# MaTouch_Devkit_Strip_Driver_V1_1.net
KiCad netlist of a schematic drawn in EAGLE
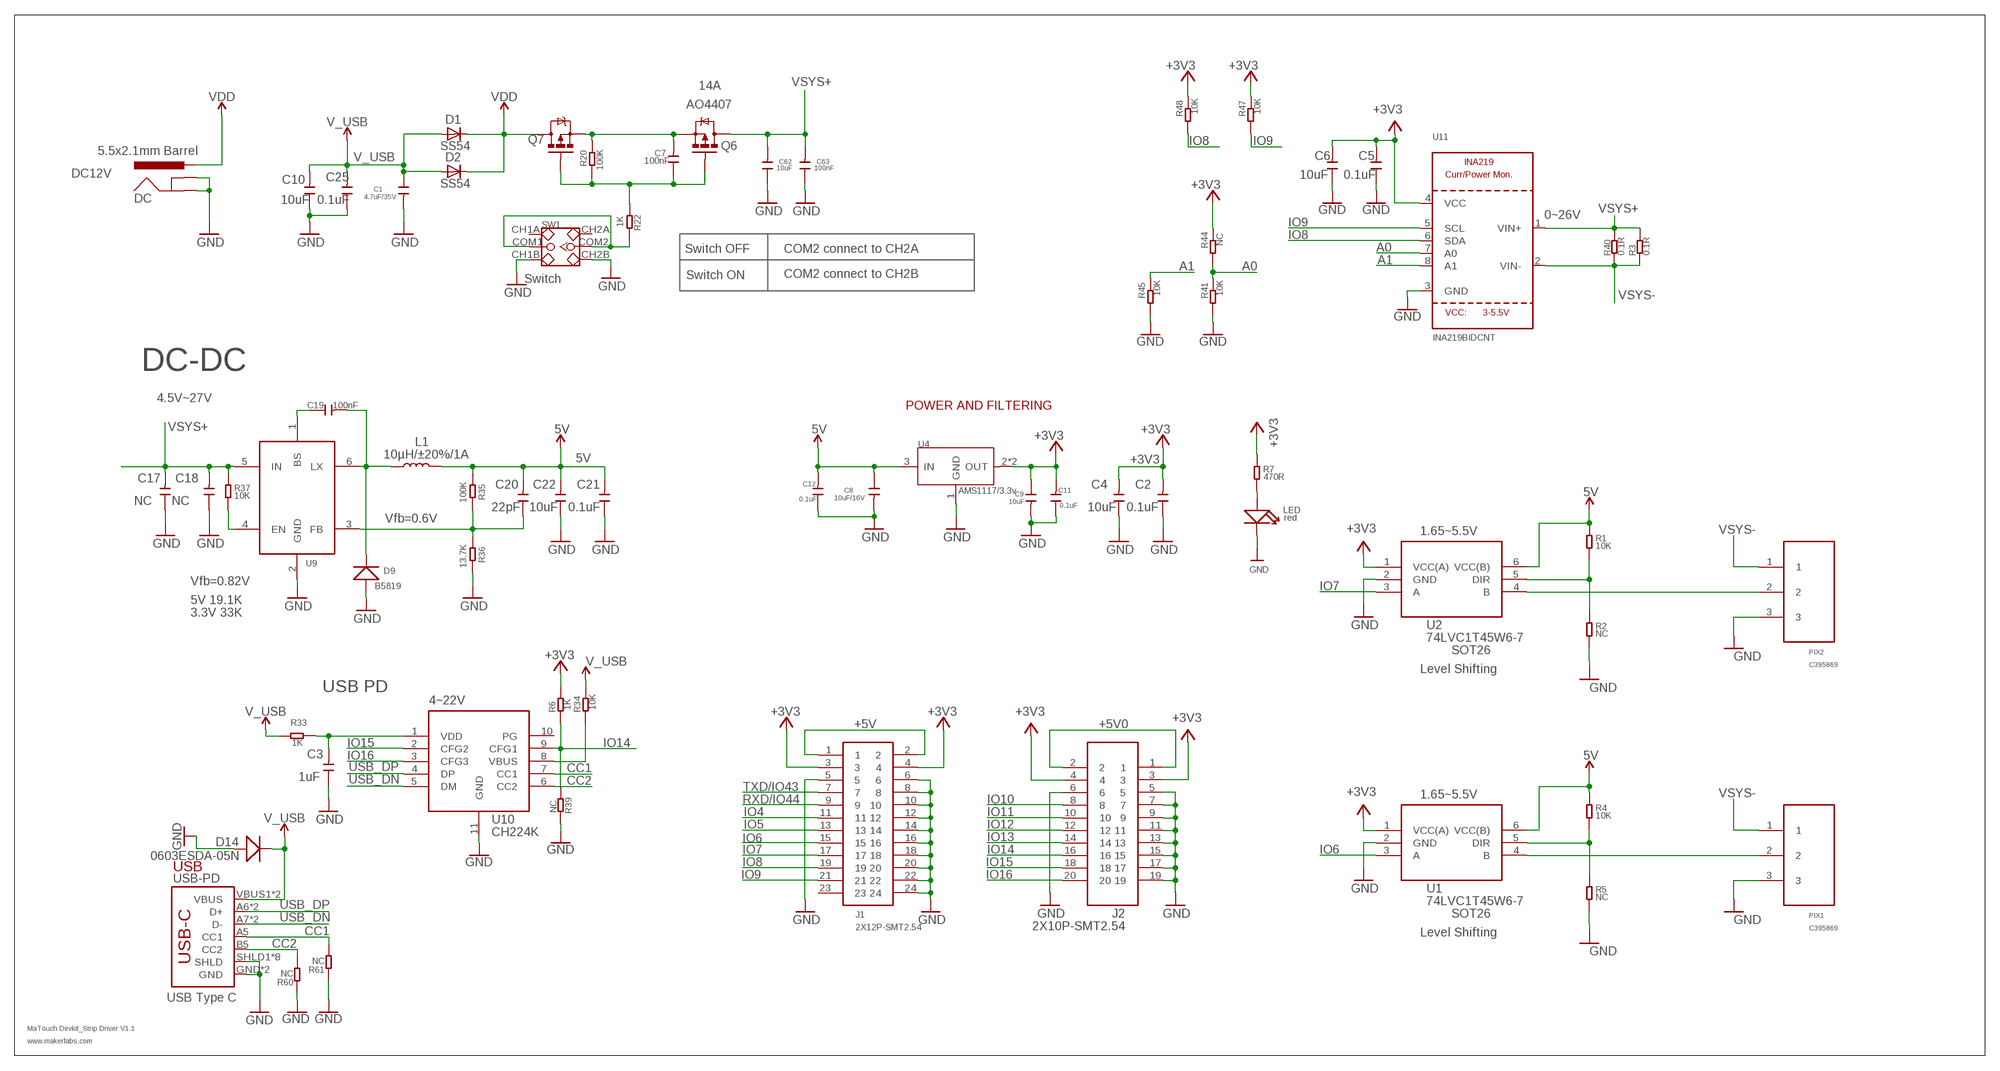
[diagram p0: schematic, sheet 1]

(export (version "E")
  (design (tool "Eeschema 10.0.6"))
  (components
    (comp (ref "C1")
      (value "4.7uF/35V")
      (footprint "eagle-import:0603")
      (libsource (lib "eagle-import") (part "C-0603"))
    )
    (comp (ref "C2")
      (value "0.1uF")
      (footprint "eagle-import:0603")
      (libsource (lib "eagle-import") (part "C-0603"))
    )
    (comp (ref "C3")
      (value "1uF")
      (footprint "eagle-import:0603")
      (libsource (lib "eagle-import") (part "C-0603"))
    )
    (comp (ref "C4")
      (value "10uF")
      (footprint "eagle-import:0603")
      (libsource (lib "eagle-import") (part "C-0603"))
    )
    (comp (ref "C5")
      (value "0.1uF")
      (footprint "eagle-import:0603")
      (libsource (lib "eagle-import") (part "C-0603"))
    )
    (comp (ref "C6")
      (value "10uF")
      (footprint "eagle-import:0603")
      (libsource (lib "eagle-import") (part "C-0603"))
    )
    (comp (ref "C7")
      (value "100nF")
      (footprint "eagle-import:0603")
      (libsource (lib "eagle-import") (part "C-0603"))
    )
    (comp (ref "C8")
      (value "10uF/16V")
      (footprint "eagle-import:0603")
      (libsource (lib "eagle-import") (part "C-0603"))
    )
    (comp (ref "C9")
      (value "10uF")
      (footprint "eagle-import:0603")
      (libsource (lib "eagle-import") (part "C-0603"))
    )
    (comp (ref "C10")
      (value "10uF")
      (footprint "eagle-import:0603")
      (libsource (lib "eagle-import") (part "C-0603"))
    )
    (comp (ref "C11")
      (value "0.1uF")
      (footprint "eagle-import:0603")
      (libsource (lib "eagle-import") (part "C-0603"))
    )
    (comp (ref "C12")
      (value "0.1uF")
      (footprint "eagle-import:0603")
      (libsource (lib "eagle-import") (part "C-0603"))
    )
    (comp (ref "C17")
      (value "NC")
      (footprint "eagle-import:0603")
      (libsource (lib "eagle-import") (part "C-0603"))
    )
    (comp (ref "C18")
      (value "NC")
      (footprint "eagle-import:0603")
      (libsource (lib "eagle-import") (part "C-0603"))
    )
    (comp (ref "C19")
      (value "100nF")
      (footprint "eagle-import:0603")
      (libsource (lib "eagle-import") (part "C-0603"))
    )
    (comp (ref "C20")
      (value "22pF")
      (footprint "eagle-import:0603")
      (libsource (lib "eagle-import") (part "C-0603"))
    )
    (comp (ref "C21")
      (value "0.1uF")
      (footprint "eagle-import:0603")
      (libsource (lib "eagle-import") (part "C-0603"))
    )
    (comp (ref "C22")
      (value "10uF")
      (footprint "eagle-import:0603")
      (libsource (lib "eagle-import") (part "C-0603"))
    )
    (comp (ref "C25")
      (value "0.1uF")
      (footprint "eagle-import:0603")
      (libsource (lib "eagle-import") (part "C-0603"))
    )
    (comp (ref "C62")
      (value "10uF")
      (footprint "eagle-import:0603")
      (libsource (lib "eagle-import") (part "C-0603"))
    )
    (comp (ref "C63")
      (value "100nF")
      (footprint "eagle-import:0603")
      (libsource (lib "eagle-import") (part "C-0603"))
    )
    (comp (ref "D1")
      (value "SS54")
      (footprint "eagle-import:DO-214AC")
      (libsource (lib "eagle-import") (part "DIODE-DO-214AC"))
    )
    (comp (ref "D2")
      (value "SS54")
      (footprint "eagle-import:DO-214AC")
      (libsource (lib "eagle-import") (part "DIODE-DO-214AC"))
    )
    (comp (ref "D9")
      (value "B5819")
      (footprint "eagle-import:SOD123")
      (libsource (lib "eagle-import") (part "D'1206'"))
    )
    (comp (ref "D14")
      (value "0603ESDA-05N")
      (footprint "eagle-import:DISCRETE_SOD523")
      (libsource (lib "eagle-import") (part "DISCRETE_D0603"))
    )
    (comp (ref "DC")
      (value "5.5x2.1mm Barrel")
      (footprint "eagle-import:POWER_JACK_SMD")
      (libsource (lib "eagle-import") (part "POWER_JACKSMD"))
    )
    (comp (ref "J1")
      (value "2X12P-SMT2.54")
      (footprint "eagle-import:2X12P-SMT2.54")
      (libsource (lib "eagle-import") (part "2X12P-SMT2.54"))
    )
    (comp (ref "J2")
      (value "2X10P-SMT2.54")
      (footprint "eagle-import:2X10P-SMT2.54")
      (libsource (lib "eagle-import") (part "2X10P-SMT2.54"))
    )
    (comp (ref "L1")
      (value "10µH/±20%/1A")
      (footprint "eagle-import:SRN6045")
      (libsource (lib "eagle-import") (part "INDUCTOR-SRN6045-33UH"))
    )
    (comp (ref "LED")
      (value "red")
      (footprint "eagle-import:DISCRETE_LED-0603")
      (libsource (lib "eagle-import") (part "DISCRETE_LED0603"))
    )
    (comp (ref "PIX1")
      (value "C395869")
      (footprint "eagle-import:PIN_3P")
      (libsource (lib "eagle-import") (part "C395869"))
    )
    (comp (ref "PIX2")
      (value "C395869")
      (footprint "eagle-import:PIN_3P")
      (libsource (lib "eagle-import") (part "C395869"))
    )
    (comp (ref "Q6")
      (value "MOSFET-PCHANNELFDS6675")
      (footprint "eagle-import:SO08")
      (libsource (lib "eagle-import") (part "MOSFET-PCHANNELFDS6675"))
    )
    (comp (ref "Q7")
      (value "MOSFET-PCHANNELFDS6675")
      (footprint "eagle-import:SO08")
      (libsource (lib "eagle-import") (part "MOSFET-PCHANNELFDS6675"))
    )
    (comp (ref "R1")
      (value "10K")
      (footprint "eagle-import:R0603")
      (libsource (lib "eagle-import") (part "R-0603"))
    )
    (comp (ref "R2")
      (value "NC")
      (footprint "eagle-import:R0603")
      (libsource (lib "eagle-import") (part "R-0603"))
    )
    (comp (ref "R3")
      (value "0.1R")
      (footprint "eagle-import:DISCRETE_R2512")
      (libsource (lib "eagle-import") (part "DISCRETE_R-2512"))
    )
    (comp (ref "R4")
      (value "10K")
      (footprint "eagle-import:R0603")
      (libsource (lib "eagle-import") (part "R-0603"))
    )
    (comp (ref "R5")
      (value "NC")
      (footprint "eagle-import:R0603")
      (libsource (lib "eagle-import") (part "R-0603"))
    )
    (comp (ref "R6")
      (value "1K")
      (footprint "eagle-import:R0603")
      (libsource (lib "eagle-import") (part "R-0603"))
    )
    (comp (ref "R7")
      (value "470R")
      (footprint "eagle-import:R0603")
      (libsource (lib "eagle-import") (part "R-0603"))
    )
    (comp (ref "R20")
      (value "100K")
      (footprint "eagle-import:R0603")
      (libsource (lib "eagle-import") (part "R-0603"))
    )
    (comp (ref "R22")
      (value "1K")
      (footprint "eagle-import:R0603")
      (libsource (lib "eagle-import") (part "R-0603"))
    )
    (comp (ref "R33")
      (value "1K")
      (footprint "eagle-import:R0603")
      (libsource (lib "eagle-import") (part "R-0603"))
    )
    (comp (ref "R34")
      (value "10K")
      (footprint "eagle-import:R0603")
      (libsource (lib "eagle-import") (part "R-0603"))
    )
    (comp (ref "R35")
      (value "100K")
      (footprint "eagle-import:R0603")
      (libsource (lib "eagle-import") (part "R-0603"))
    )
    (comp (ref "R36")
      (value "13.7K")
      (footprint "eagle-import:R0603")
      (libsource (lib "eagle-import") (part "R-0603"))
    )
    (comp (ref "R37")
      (value "10K")
      (footprint "eagle-import:R0603")
      (libsource (lib "eagle-import") (part "R-0603"))
    )
    (comp (ref "R39")
      (value "NC")
      (footprint "eagle-import:R0603")
      (libsource (lib "eagle-import") (part "R-0603"))
    )
    (comp (ref "R40")
      (value "0.1R")
      (footprint "eagle-import:DISCRETE_R2512")
      (libsource (lib "eagle-import") (part "DISCRETE_R-2512"))
    )
    (comp (ref "R41")
      (value "10K")
      (footprint "eagle-import:R0603")
      (libsource (lib "eagle-import") (part "R-0603"))
    )
    (comp (ref "R44")
      (value "NC")
      (footprint "eagle-import:R0603")
      (libsource (lib "eagle-import") (part "R-0603"))
    )
    (comp (ref "R45")
      (value "10K")
      (footprint "eagle-import:R0603")
      (libsource (lib "eagle-import") (part "R-0603"))
    )
    (comp (ref "R47")
      (value "10K")
      (footprint "eagle-import:R0603")
      (libsource (lib "eagle-import") (part "R-0603"))
    )
    (comp (ref "R48")
      (value "10K")
      (footprint "eagle-import:R0603")
      (libsource (lib "eagle-import") (part "R-0603"))
    )
    (comp (ref "R60")
      (value "NC")
      (footprint "eagle-import:DISCRETE_R0603")
      (libsource (lib "eagle-import") (part "DISCRETE_R-0603"))
    )
    (comp (ref "R61")
      (value "NC")
      (footprint "eagle-import:DISCRETE_R0603")
      (libsource (lib "eagle-import") (part "DISCRETE_R-0603"))
    )
    (comp (ref "SW1")
      (value "SWITCH-2CH-6P'90D'")
      (footprint "eagle-import:6P-2CH-2.54-9.0X3.6-90D")
      (libsource (lib "eagle-import") (part "SWITCH-2CH-6P'90D'"))
    )
    (comp (ref "U1")
      (value "74LVC1T45W6-7")
      (footprint "eagle-import:SOT-23-6")
      (libsource (lib "eagle-import") (part "74LVC1T45W6-7"))
    )
    (comp (ref "U2")
      (value "74LVC1T45W6-7")
      (footprint "eagle-import:SOT-23-6")
      (libsource (lib "eagle-import") (part "74LVC1T45W6-7"))
    )
    (comp (ref "U4")
      (value "AMS1117/3.3v")
      (footprint "eagle-import:SOT89")
      (libsource (lib "eagle-import") (part "LD1117'SOT89'"))
    )
    (comp (ref "U9")
      (value "SY8201ABC")
      (footprint "eagle-import:SOT-23-6")
      (libsource (lib "eagle-import") (part "SY8201ABC"))
    )
    (comp (ref "U10")
      (value "CH224K")
      (footprint "eagle-import:ESSOP-10-150MIL")
      (libsource (lib "eagle-import") (part "CH224K"))
    )
    (comp (ref "U11")
      (value "INA219BIDCNT")
      (footprint "eagle-import:SOT23-8")
      (libsource (lib "eagle-import") (part "INA219"))
    )
    (comp (ref "USB-PD")
      (value "USB_C5")
      (footprint "eagle-import:USB-C-16P-5")
      (libsource (lib "eagle-import") (part "USB_C5"))
    )
  )
  (nets
    (net (code "1") (name "+3V3") (class "Default")
      (node (ref "C11") (pin "2") (pinfunction "2_2") (pintype "passive"))
      (node (ref "C2") (pin "2") (pinfunction "2_2") (pintype "passive"))
      (node (ref "C4") (pin "2") (pinfunction "2_2") (pintype "passive"))
      (node (ref "C5") (pin "2") (pinfunction "2_2") (pintype "passive"))
      (node (ref "C6") (pin "2") (pinfunction "2_2") (pintype "passive"))
      (node (ref "C9") (pin "1") (pinfunction "1_1") (pintype "passive"))
      (node (ref "J1") (pin "3") (pinfunction "3_3") (pintype "bidirectional"))
      (node (ref "J1") (pin "4") (pinfunction "4_4") (pintype "bidirectional"))
      (node (ref "J2") (pin "3") (pinfunction "3_3") (pintype "bidirectional"))
      (node (ref "J2") (pin "4") (pinfunction "4_4") (pintype "bidirectional"))
      (node (ref "R44") (pin "2") (pinfunction "2_2") (pintype "passive"))
      (node (ref "R47") (pin "2") (pinfunction "2_2") (pintype "passive"))
      (node (ref "R48") (pin "2") (pinfunction "2_2") (pintype "passive"))
      (node (ref "R6") (pin "2") (pinfunction "2_2") (pintype "passive"))
      (node (ref "R7") (pin "1") (pinfunction "1_1") (pintype "passive"))
      (node (ref "U1") (pin "1") (pinfunction "VCC(A)_1") (pintype "bidirectional"))
      (node (ref "U11") (pin "4") (pinfunction "VCC_4") (pintype "power_in"))
      (node (ref "U2") (pin "1") (pinfunction "VCC(A)_1") (pintype "bidirectional"))
      (node (ref "U4") (pin "2") (pinfunction "OUT_2") (pintype "bidirectional"))
      (node (ref "U4") (pin "4") (pinfunction "OUT_4") (pintype "bidirectional"))
    )
    (net (code "2") (name "/+5V") (class "Default")
      (node (ref "J1") (pin "1") (pinfunction "1_1") (pintype "bidirectional"))
      (node (ref "J1") (pin "2") (pinfunction "2_2") (pintype "bidirectional"))
    )
    (net (code "3") (name "/+5V0") (class "Default")
      (node (ref "J2") (pin "1") (pinfunction "1_1") (pintype "bidirectional"))
      (node (ref "J2") (pin "2") (pinfunction "2_2") (pintype "bidirectional"))
    )
    (net (code "4") (name "/A0") (class "Default")
      (node (ref "R41") (pin "2") (pinfunction "2_2") (pintype "passive"))
      (node (ref "R44") (pin "1") (pinfunction "1_1") (pintype "passive"))
      (node (ref "U11") (pin "7") (pinfunction "A0_7") (pintype "bidirectional"))
    )
    (net (code "5") (name "/A1") (class "Default")
      (node (ref "R45") (pin "2") (pinfunction "2_2") (pintype "passive"))
      (node (ref "U11") (pin "8") (pinfunction "A1_8") (pintype "bidirectional"))
    )
    (net (code "6") (name "/CC1") (class "Default")
      (node (ref "R61") (pin "2") (pinfunction "2_2") (pintype "passive"))
      (node (ref "U10") (pin "7") (pinfunction "CC1_7") (pintype "bidirectional"))
      (node (ref "USB-PD") (pin "A5") (pinfunction "CC1_A5") (pintype "bidirectional"))
    )
    (net (code "7") (name "/CC2") (class "Default")
      (node (ref "R60") (pin "2") (pinfunction "2_2") (pintype "passive"))
      (node (ref "U10") (pin "6") (pinfunction "CC2_6") (pintype "bidirectional"))
      (node (ref "USB-PD") (pin "B5") (pinfunction "CC2_B5") (pintype "bidirectional"))
    )
    (net (code "8") (name "/IO4") (class "Default")
      (node (ref "J1") (pin "11") (pinfunction "11_11") (pintype "bidirectional"))
    )
    (net (code "9") (name "/IO5") (class "Default")
      (node (ref "J1") (pin "13") (pinfunction "13_13") (pintype "bidirectional"))
    )
    (net (code "10") (name "/IO6") (class "Default")
      (node (ref "J1") (pin "15") (pinfunction "15_15") (pintype "bidirectional"))
      (node (ref "U1") (pin "3") (pinfunction "A_3") (pintype "bidirectional"))
    )
    (net (code "11") (name "/IO7") (class "Default")
      (node (ref "J1") (pin "17") (pinfunction "17_17") (pintype "bidirectional"))
      (node (ref "U2") (pin "3") (pinfunction "A_3") (pintype "bidirectional"))
    )
    (net (code "12") (name "/IO8") (class "Default")
      (node (ref "J1") (pin "19") (pinfunction "19_19") (pintype "bidirectional"))
      (node (ref "R48") (pin "1") (pinfunction "1_1") (pintype "passive"))
      (node (ref "U11") (pin "6") (pinfunction "SDA_6") (pintype "bidirectional"))
    )
    (net (code "13") (name "/IO9") (class "Default")
      (node (ref "J1") (pin "21") (pinfunction "21_21") (pintype "bidirectional"))
      (node (ref "R47") (pin "1") (pinfunction "1_1") (pintype "passive"))
      (node (ref "U11") (pin "5") (pinfunction "SCL_5") (pintype "bidirectional"))
    )
    (net (code "14") (name "/IO10") (class "Default")
      (node (ref "J2") (pin "8") (pinfunction "8_8") (pintype "bidirectional"))
    )
    (net (code "15") (name "/IO11") (class "Default")
      (node (ref "J2") (pin "10") (pinfunction "10_10") (pintype "bidirectional"))
    )
    (net (code "16") (name "/IO12") (class "Default")
      (node (ref "J2") (pin "12") (pinfunction "12_12") (pintype "bidirectional"))
    )
    (net (code "17") (name "/IO13") (class "Default")
      (node (ref "J2") (pin "14") (pinfunction "14_14") (pintype "bidirectional"))
    )
    (net (code "18") (name "/IO14") (class "Default")
      (node (ref "J2") (pin "16") (pinfunction "16_16") (pintype "bidirectional"))
      (node (ref "R39") (pin "1") (pinfunction "1_1") (pintype "passive"))
      (node (ref "R6") (pin "1") (pinfunction "1_1") (pintype "passive"))
      (node (ref "U10") (pin "9") (pinfunction "CFG1_9") (pintype "bidirectional"))
    )
    (net (code "19") (name "/IO15") (class "Default")
      (node (ref "J2") (pin "18") (pinfunction "18_18") (pintype "bidirectional"))
      (node (ref "U10") (pin "2") (pinfunction "CFG2_2") (pintype "bidirectional"))
    )
    (net (code "20") (name "/IO16") (class "Default")
      (node (ref "J2") (pin "20") (pinfunction "20_20") (pintype "bidirectional"))
      (node (ref "U10") (pin "3") (pinfunction "CFG3_3") (pintype "bidirectional"))
    )
    (net (code "21") (name "/RXD{slash}IO44") (class "Default")
      (node (ref "J1") (pin "9") (pinfunction "9_9") (pintype "bidirectional"))
    )
    (net (code "22") (name "/TXD{slash}IO43") (class "Default")
      (node (ref "J1") (pin "7") (pinfunction "7_7") (pintype "bidirectional"))
    )
    (net (code "23") (name "/USB_DN") (class "Default")
      (node (ref "U10") (pin "5") (pinfunction "DM_5") (pintype "bidirectional"))
      (node (ref "USB-PD") (pin "A7") (pinfunction "D-_A7") (pintype "bidirectional"))
      (node (ref "USB-PD") (pin "B7") (pinfunction "D-_B7") (pintype "bidirectional"))
    )
    (net (code "24") (name "/USB_DP") (class "Default")
      (node (ref "U10") (pin "4") (pinfunction "DP_4") (pintype "bidirectional"))
      (node (ref "USB-PD") (pin "A6") (pinfunction "D+_A6") (pintype "bidirectional"))
      (node (ref "USB-PD") (pin "B6") (pinfunction "D+_B6") (pintype "bidirectional"))
    )
    (net (code "25") (name "/VSYS+") (class "Default")
      (node (ref "C17") (pin "2") (pinfunction "2_2") (pintype "passive"))
      (node (ref "C18") (pin "2") (pinfunction "2_2") (pintype "passive"))
      (node (ref "C62") (pin "2") (pinfunction "2_2") (pintype "passive"))
      (node (ref "C63") (pin "2") (pinfunction "2_2") (pintype "passive"))
      (node (ref "Q6") (pin "5") (pinfunction "D_5") (pintype "passive"))
      (node (ref "Q6") (pin "6") (pinfunction "D_6") (pintype "passive"))
      (node (ref "Q6") (pin "7") (pinfunction "D_7") (pintype "passive"))
      (node (ref "Q6") (pin "8") (pinfunction "D_8") (pintype "passive"))
      (node (ref "R3") (pin "2") (pinfunction "2_2") (pintype "passive"))
      (node (ref "R37") (pin "1") (pinfunction "1_1") (pintype "passive"))
      (node (ref "R40") (pin "2") (pinfunction "2_2") (pintype "passive"))
      (node (ref "U11") (pin "1") (pinfunction "VIN+_1") (pintype "bidirectional"))
      (node (ref "U9") (pin "5") (pinfunction "IN_5") (pintype "bidirectional"))
    )
    (net (code "26") (name "/VSYS-") (class "Default")
      (node (ref "PIX1") (pin "1") (pinfunction "1_1") (pintype "bidirectional"))
      (node (ref "PIX2") (pin "1") (pinfunction "1_1") (pintype "bidirectional"))
      (node (ref "R3") (pin "1") (pinfunction "1_1") (pintype "passive"))
      (node (ref "R40") (pin "1") (pinfunction "1_1") (pintype "passive"))
      (node (ref "U11") (pin "2") (pinfunction "VIN-_2") (pintype "bidirectional"))
    )
    (net (code "27") (name "5V") (class "Default")
      (node (ref "C12") (pin "2") (pinfunction "2_2") (pintype "passive"))
      (node (ref "C20") (pin "2") (pinfunction "2_2") (pintype "passive"))
      (node (ref "C21") (pin "2") (pinfunction "2_2") (pintype "passive"))
      (node (ref "C22") (pin "2") (pinfunction "2_2") (pintype "passive"))
      (node (ref "C8") (pin "1") (pinfunction "1_1") (pintype "passive"))
      (node (ref "L1") (pin "2") (pinfunction "2_2") (pintype "passive"))
      (node (ref "R1") (pin "1") (pinfunction "1_1") (pintype "passive"))
      (node (ref "R35") (pin "1") (pinfunction "1_1") (pintype "passive"))
      (node (ref "R4") (pin "1") (pinfunction "1_1") (pintype "passive"))
      (node (ref "U1") (pin "6") (pinfunction "VCC(B)_6") (pintype "bidirectional"))
      (node (ref "U2") (pin "6") (pinfunction "VCC(B)_6") (pintype "bidirectional"))
      (node (ref "U4") (pin "3") (pinfunction "IN_3") (pintype "bidirectional"))
    )
    (net (code "28") (name "GND") (class "Default")
      (node (ref "C1") (pin "2") (pinfunction "2_2") (pintype "passive"))
      (node (ref "C10") (pin "1") (pinfunction "1_1") (pintype "passive"))
      (node (ref "C11") (pin "1") (pinfunction "1_1") (pintype "passive"))
      (node (ref "C12") (pin "1") (pinfunction "1_1") (pintype "passive"))
      (node (ref "C17") (pin "1") (pinfunction "1_1") (pintype "passive"))
      (node (ref "C18") (pin "1") (pinfunction "1_1") (pintype "passive"))
      (node (ref "C2") (pin "1") (pinfunction "1_1") (pintype "passive"))
      (node (ref "C21") (pin "1") (pinfunction "1_1") (pintype "passive"))
      (node (ref "C22") (pin "1") (pinfunction "1_1") (pintype "passive"))
      (node (ref "C25") (pin "1") (pinfunction "1_1") (pintype "passive"))
      (node (ref "C3") (pin "1") (pinfunction "1_1") (pintype "passive"))
      (node (ref "C4") (pin "1") (pinfunction "1_1") (pintype "passive"))
      (node (ref "C5") (pin "1") (pinfunction "1_1") (pintype "passive"))
      (node (ref "C6") (pin "1") (pinfunction "1_1") (pintype "passive"))
      (node (ref "C62") (pin "1") (pinfunction "1_1") (pintype "passive"))
      (node (ref "C63") (pin "1") (pinfunction "1_1") (pintype "passive"))
      (node (ref "C8") (pin "2") (pinfunction "2_2") (pintype "passive"))
      (node (ref "C9") (pin "2") (pinfunction "2_2") (pintype "passive"))
      (node (ref "D14") (pin "+") (pinfunction "+_+") (pintype "passive"))
      (node (ref "D9") (pin "+") (pinfunction "+_+") (pintype "passive"))
      (node (ref "DC") (pin "GND") (pinfunction "GNDBREAK_GND") (pintype "bidirectional"))
      (node (ref "DC") (pin "P$4") (pinfunction "GND_P$4") (pintype "bidirectional"))
      (node (ref "J1") (pin "10") (pinfunction "10_10") (pintype "bidirectional"))
      (node (ref "J1") (pin "12") (pinfunction "12_12") (pintype "bidirectional"))
      (node (ref "J1") (pin "14") (pinfunction "14_14") (pintype "bidirectional"))
      (node (ref "J1") (pin "16") (pinfunction "16_16") (pintype "bidirectional"))
      (node (ref "J1") (pin "18") (pinfunction "18_18") (pintype "bidirectional"))
      (node (ref "J1") (pin "20") (pinfunction "20_20") (pintype "bidirectional"))
      (node (ref "J1") (pin "22") (pinfunction "22_22") (pintype "bidirectional"))
      (node (ref "J1") (pin "24") (pinfunction "24_24") (pintype "bidirectional"))
      (node (ref "J1") (pin "5") (pinfunction "5_5") (pintype "bidirectional"))
      (node (ref "J1") (pin "6") (pinfunction "6_6") (pintype "bidirectional"))
      (node (ref "J1") (pin "8") (pinfunction "8_8") (pintype "bidirectional"))
      (node (ref "J2") (pin "11") (pinfunction "11_11") (pintype "bidirectional"))
      (node (ref "J2") (pin "13") (pinfunction "13_13") (pintype "bidirectional"))
      (node (ref "J2") (pin "15") (pinfunction "15_15") (pintype "bidirectional"))
      (node (ref "J2") (pin "17") (pinfunction "17_17") (pintype "bidirectional"))
      (node (ref "J2") (pin "19") (pinfunction "19_19") (pintype "bidirectional"))
      (node (ref "J2") (pin "5") (pinfunction "5_5") (pintype "bidirectional"))
      (node (ref "J2") (pin "6") (pinfunction "6_6") (pintype "bidirectional"))
      (node (ref "J2") (pin "7") (pinfunction "7_7") (pintype "bidirectional"))
      (node (ref "J2") (pin "9") (pinfunction "9_9") (pintype "bidirectional"))
      (node (ref "LED") (pin "-") (pinfunction "-_-") (pintype "passive"))
      (node (ref "PIX1") (pin "3") (pinfunction "3_3") (pintype "bidirectional"))
      (node (ref "PIX2") (pin "3") (pinfunction "3_3") (pintype "bidirectional"))
      (node (ref "R2") (pin "2") (pinfunction "2_2") (pintype "passive"))
      (node (ref "R36") (pin "2") (pinfunction "2_2") (pintype "passive"))
      (node (ref "R39") (pin "2") (pinfunction "2_2") (pintype "passive"))
      (node (ref "R41") (pin "1") (pinfunction "1_1") (pintype "passive"))
      (node (ref "R45") (pin "1") (pinfunction "1_1") (pintype "passive"))
      (node (ref "R5") (pin "2") (pinfunction "2_2") (pintype "passive"))
      (node (ref "R60") (pin "1") (pinfunction "1_1") (pintype "passive"))
      (node (ref "R61") (pin "1") (pinfunction "1_1") (pintype "passive"))
      (node (ref "SW1") (pin "CH1B") (pinfunction "CH1B_CH1B") (pintype "bidirectional"))
      (node (ref "SW1") (pin "CH2B") (pinfunction "CH2B_CH2B") (pintype "bidirectional"))
      (node (ref "U1") (pin "2") (pinfunction "GND_2") (pintype "bidirectional"))
      (node (ref "U10") (pin "11") (pinfunction "GND_11") (pintype "bidirectional"))
      (node (ref "U11") (pin "3") (pinfunction "GND_3") (pintype "power_in"))
      (node (ref "U2") (pin "2") (pinfunction "GND_2") (pintype "bidirectional"))
      (node (ref "U4") (pin "1") (pinfunction "GND_1") (pintype "bidirectional"))
      (node (ref "U9") (pin "2") (pinfunction "GND_2") (pintype "bidirectional"))
      (node (ref "USB-PD") (pin "GND") (pinfunction "GND_GND") (pintype "bidirectional"))
      (node (ref "USB-PD") (pin "GND2") (pinfunction "GND_GND2") (pintype "bidirectional"))
      (node (ref "USB-PD") (pin "SHLD1") (pinfunction "SHLD_SHLD1") (pintype "bidirectional"))
      (node (ref "USB-PD") (pin "SHLD2") (pinfunction "SHLD_SHLD2") (pintype "bidirectional"))
      (node (ref "USB-PD") (pin "SHLD3") (pinfunction "SHLD_SHLD3") (pintype "bidirectional"))
      (node (ref "USB-PD") (pin "SHLD4") (pinfunction "SHLD_SHLD4") (pintype "bidirectional"))
      (node (ref "USB-PD") (pin "SHLD5") (pinfunction "SHLD_SHLD5") (pintype "bidirectional"))
      (node (ref "USB-PD") (pin "SHLD6") (pinfunction "SHLD_SHLD6") (pintype "bidirectional"))
      (node (ref "USB-PD") (pin "SHLD7") (pinfunction "SHLD_SHLD7") (pintype "bidirectional"))
      (node (ref "USB-PD") (pin "SHLD8") (pinfunction "SHLD_SHLD8") (pintype "bidirectional"))
    )
    (net (code "29") (name "Net-(C7-Pad2)") (class "Default")
      (node (ref "C7") (pin "2") (pinfunction "2_2") (pintype "passive"))
      (node (ref "Q6") (pin "1") (pinfunction "S_1") (pintype "passive"))
      (node (ref "Q6") (pin "2") (pinfunction "S_2") (pintype "passive"))
      (node (ref "Q6") (pin "3") (pinfunction "S_3") (pintype "passive"))
      (node (ref "Q7") (pin "1") (pinfunction "S_1") (pintype "passive"))
      (node (ref "Q7") (pin "2") (pinfunction "S_2") (pintype "passive"))
      (node (ref "Q7") (pin "3") (pinfunction "S_3") (pintype "passive"))
      (node (ref "R20") (pin "1") (pinfunction "1_1") (pintype "passive"))
    )
    (net (code "30") (name "Net-(LED-Pad+)") (class "Default")
      (node (ref "LED") (pin "+") (pinfunction "+_+") (pintype "passive"))
      (node (ref "R7") (pin "2") (pinfunction "2_2") (pintype "passive"))
    )
    (net (code "31") (name "Net-(Q6-G)") (class "Default")
      (node (ref "C7") (pin "1") (pinfunction "1_1") (pintype "passive"))
      (node (ref "Q6") (pin "4") (pinfunction "G_4") (pintype "passive"))
      (node (ref "Q7") (pin "4") (pinfunction "G_4") (pintype "passive"))
      (node (ref "R20") (pin "2") (pinfunction "2_2") (pintype "passive"))
      (node (ref "R22") (pin "2") (pinfunction "2_2") (pintype "passive"))
    )
    (net (code "32") (name "Net-(R22-Pad1)") (class "Default")
      (node (ref "R22") (pin "1") (pinfunction "1_1") (pintype "passive"))
      (node (ref "SW1") (pin "COM1") (pinfunction "COM1_COM1") (pintype "bidirectional"))
      (node (ref "SW1") (pin "COM2") (pinfunction "COM2_COM2") (pintype "bidirectional"))
    )
    (net (code "33") (name "Net-(U1-B)") (class "Default")
      (node (ref "PIX1") (pin "2") (pinfunction "2_2") (pintype "bidirectional"))
      (node (ref "U1") (pin "4") (pinfunction "B_4") (pintype "bidirectional"))
    )
    (net (code "34") (name "Net-(U1-DIR)") (class "Default")
      (node (ref "R4") (pin "2") (pinfunction "2_2") (pintype "passive"))
      (node (ref "R5") (pin "1") (pinfunction "1_1") (pintype "passive"))
      (node (ref "U1") (pin "5") (pinfunction "DIR_5") (pintype "bidirectional"))
    )
    (net (code "35") (name "Net-(U2-B)") (class "Default")
      (node (ref "PIX2") (pin "2") (pinfunction "2_2") (pintype "bidirectional"))
      (node (ref "U2") (pin "4") (pinfunction "B_4") (pintype "bidirectional"))
    )
    (net (code "36") (name "Net-(U2-DIR)") (class "Default")
      (node (ref "R1") (pin "2") (pinfunction "2_2") (pintype "passive"))
      (node (ref "R2") (pin "1") (pinfunction "1_1") (pintype "passive"))
      (node (ref "U2") (pin "5") (pinfunction "DIR_5") (pintype "bidirectional"))
    )
    (net (code "37") (name "Net-(U9-BS)") (class "Default")
      (node (ref "C19") (pin "1") (pinfunction "1_1") (pintype "passive"))
      (node (ref "U9") (pin "1") (pinfunction "BS_1") (pintype "bidirectional"))
    )
    (net (code "38") (name "Net-(U9-EN)") (class "Default")
      (node (ref "R37") (pin "2") (pinfunction "2_2") (pintype "passive"))
      (node (ref "U9") (pin "4") (pinfunction "EN_4") (pintype "bidirectional"))
    )
    (net (code "39") (name "Net-(U9-FB)") (class "Default")
      (node (ref "C20") (pin "1") (pinfunction "1_1") (pintype "passive"))
      (node (ref "R35") (pin "2") (pinfunction "2_2") (pintype "passive"))
      (node (ref "R36") (pin "1") (pinfunction "1_1") (pintype "passive"))
      (node (ref "U9") (pin "3") (pinfunction "FB_3") (pintype "bidirectional"))
    )
    (net (code "40") (name "Net-(U9-LX)") (class "Default")
      (node (ref "C19") (pin "2") (pinfunction "2_2") (pintype "passive"))
      (node (ref "D9") (pin "-") (pinfunction "-_-") (pintype "passive"))
      (node (ref "L1") (pin "1") (pinfunction "1_1") (pintype "passive"))
      (node (ref "U9") (pin "6") (pinfunction "LX_6") (pintype "bidirectional"))
    )
    (net (code "41") (name "Net-(U10-VBUS)") (class "Default")
      (node (ref "R34") (pin "1") (pinfunction "1_1") (pintype "passive"))
      (node (ref "U10") (pin "8") (pinfunction "VBUS_8") (pintype "bidirectional"))
    )
    (net (code "42") (name "Net-(U10-VDD)") (class "Default")
      (node (ref "C3") (pin "2") (pinfunction "2_2") (pintype "passive"))
      (node (ref "R33") (pin "2") (pinfunction "2_2") (pintype "passive"))
      (node (ref "U10") (pin "1") (pinfunction "VDD_1") (pintype "bidirectional"))
    )
    (net (code "43") (name "VDD") (class "Default")
      (node (ref "D1") (pin "C") (pinfunction "C_C") (pintype "passive"))
      (node (ref "D2") (pin "C") (pinfunction "C_C") (pintype "passive"))
      (node (ref "DC") (pin "VIN0") (pinfunction "PWR_VIN0") (pintype "bidirectional"))
      (node (ref "Q7") (pin "5") (pinfunction "D_5") (pintype "passive"))
      (node (ref "Q7") (pin "6") (pinfunction "D_6") (pintype "passive"))
      (node (ref "Q7") (pin "7") (pinfunction "D_7") (pintype "passive"))
      (node (ref "Q7") (pin "8") (pinfunction "D_8") (pintype "passive"))
    )
    (net (code "44") (name "V_USB") (class "Default")
      (node (ref "C1") (pin "1") (pinfunction "1_1") (pintype "passive"))
      (node (ref "C10") (pin "2") (pinfunction "2_2") (pintype "passive"))
      (node (ref "C25") (pin "2") (pinfunction "2_2") (pintype "passive"))
      (node (ref "D1") (pin "A") (pinfunction "A_A") (pintype "passive"))
      (node (ref "D14") (pin "-") (pinfunction "-_-") (pintype "passive"))
      (node (ref "D2") (pin "A") (pinfunction "A_A") (pintype "passive"))
      (node (ref "R33") (pin "1") (pinfunction "1_1") (pintype "passive"))
      (node (ref "R34") (pin "2") (pinfunction "2_2") (pintype "passive"))
      (node (ref "USB-PD") (pin "VBUS1") (pinfunction "VBUS_VBUS1") (pintype "bidirectional"))
      (node (ref "USB-PD") (pin "VBUS2") (pinfunction "VBUS_VBUS2") (pintype "bidirectional"))
    )
    (net (code "45") (name "unconnected-(J1-Pad23)") (class "Default")
      (node (ref "J1") (pin "23") (pinfunction "23_23") (pintype "bidirectional"))
    )
    (net (code "46") (name "unconnected-(SW1-PadCH1A)") (class "Default")
      (node (ref "SW1") (pin "CH1A") (pinfunction "CH1A_CH1A") (pintype "bidirectional"))
    )
    (net (code "47") (name "unconnected-(SW1-PadCH2A)") (class "Default")
      (node (ref "SW1") (pin "CH2A") (pinfunction "CH2A_CH2A") (pintype "bidirectional"))
    )
    (net (code "48") (name "unconnected-(U10-PG-Pad10)") (class "Default")
      (node (ref "U10") (pin "10") (pinfunction "PG_10") (pintype "bidirectional"))
    )
  )
)
